# driver_board_one_module_pic_v3_1.net
KiCad netlist of a schematic drawn in EAGLE
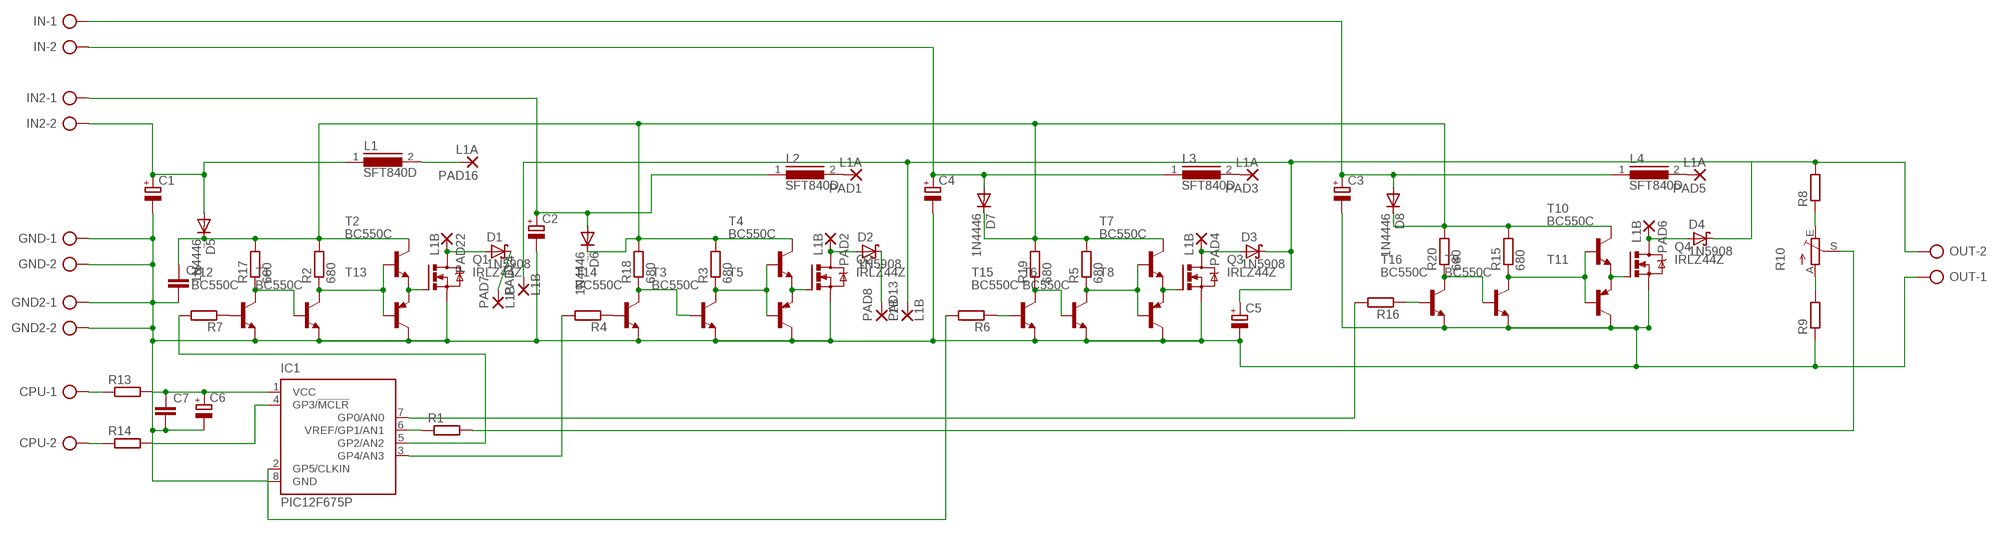
[diagram p0: schematic, sheet 1]

(export (version "E")
  (design (tool "Eeschema 10.0.6"))
  (components
    (comp (ref "C1")
      (value "CPOL-EUE5-8.5")
      (footprint "eagle-import:E5-8,5")
      (libsource (lib "eagle-import") (part "CPOL-EUE5-8.5"))
    )
    (comp (ref "C2")
      (value "CPOL-EUE5-8.5")
      (footprint "eagle-import:E5-8,5")
      (libsource (lib "eagle-import") (part "CPOL-EUE5-8.5"))
    )
    (comp (ref "C3")
      (value "CPOL-EUE5-8.5")
      (footprint "eagle-import:E5-8,5")
      (libsource (lib "eagle-import") (part "CPOL-EUE5-8.5"))
    )
    (comp (ref "C4")
      (value "CPOL-EUE5-8.5")
      (footprint "eagle-import:E5-8,5")
      (libsource (lib "eagle-import") (part "CPOL-EUE5-8.5"))
    )
    (comp (ref "C5")
      (value "CPOL-EUE5-8.5")
      (footprint "eagle-import:E5-8,5")
      (libsource (lib "eagle-import") (part "CPOL-EUE5-8.5"))
    )
    (comp (ref "C6")
      (value "CPOL-EUE5-8.5")
      (footprint "eagle-import:E5-8,5")
      (libsource (lib "eagle-import") (part "CPOL-EUE5-8.5"))
    )
    (comp (ref "C7")
      (value "C-EUC1206K")
      (footprint "eagle-import:C1206K")
      (libsource (lib "eagle-import") (part "C-EUC1206K"))
    )
    (comp (ref "C8")
      (value "C-EU050-045X075")
      (footprint "eagle-import:C050-045X075")
      (libsource (lib "eagle-import") (part "C-EU050-045X075"))
    )
    (comp (ref "CPU")
      (value "AK300/2")
      (footprint "eagle-import:AK300_2")
      (libsource (lib "eagle-import") (part "AK300/2"))
    )
    (comp (ref "D1")
      (value "1N5908")
      (footprint "eagle-import:C4111-15")
      (libsource (lib "eagle-import") (part "1N5908"))
    )
    (comp (ref "D2")
      (value "1N5908")
      (footprint "eagle-import:C4111-15")
      (libsource (lib "eagle-import") (part "1N5908"))
    )
    (comp (ref "D3")
      (value "1N5908")
      (footprint "eagle-import:C4111-15")
      (libsource (lib "eagle-import") (part "1N5908"))
    )
    (comp (ref "D4")
      (value "1N5908")
      (footprint "eagle-import:C4111-15")
      (libsource (lib "eagle-import") (part "1N5908"))
    )
    (comp (ref "D5")
      (value "1N4446")
      (footprint "eagle-import:DO35-10")
      (libsource (lib "eagle-import") (part "1N4446"))
    )
    (comp (ref "D6")
      (value "1N4446")
      (footprint "eagle-import:DO35-10")
      (libsource (lib "eagle-import") (part "1N4446"))
    )
    (comp (ref "D7")
      (value "1N4446")
      (footprint "eagle-import:DO35-10")
      (libsource (lib "eagle-import") (part "1N4446"))
    )
    (comp (ref "D8")
      (value "1N4446")
      (footprint "eagle-import:DO35-10")
      (libsource (lib "eagle-import") (part "1N4446"))
    )
    (comp (ref "GND")
      (value "AK300/2")
      (footprint "eagle-import:AK300_2")
      (libsource (lib "eagle-import") (part "AK300/2"))
    )
    (comp (ref "GND2")
      (value "AK300/2")
      (footprint "eagle-import:AK300_2")
      (libsource (lib "eagle-import") (part "AK300/2"))
    )
    (comp (ref "IC1")
      (value "PIC12F675P")
      (footprint "eagle-import:DIL8")
      (fields (field (name "MF") "MICROCHIP") (field (name "MPN") "PIC12F675-E/P"))
      (libsource (lib "eagle-import") (part "PIC12F675P"))
    )
    (comp (ref "IN")
      (value "AK300/2")
      (footprint "eagle-import:AK300_2")
      (libsource (lib "eagle-import") (part "AK300/2"))
    )
    (comp (ref "IN2")
      (value "AK300/2")
      (footprint "eagle-import:AK300_2")
      (libsource (lib "eagle-import") (part "AK300/2"))
    )
    (comp (ref "L1")
      (value "SFT840D")
      (footprint "eagle-import:SFT840D")
      (libsource (lib "eagle-import") (part "SFT840D"))
    )
    (comp (ref "L2")
      (value "SFT840D")
      (footprint "eagle-import:SFT840D")
      (libsource (lib "eagle-import") (part "SFT840D"))
    )
    (comp (ref "L3")
      (value "SFT840D")
      (footprint "eagle-import:SFT840D")
      (libsource (lib "eagle-import") (part "SFT840D"))
    )
    (comp (ref "L4")
      (value "SFT840D")
      (footprint "eagle-import:SFT840D")
      (libsource (lib "eagle-import") (part "SFT840D"))
    )
    (comp (ref "OUT")
      (value "AK300/2")
      (footprint "eagle-import:AK300_2")
      (libsource (lib "eagle-import") (part "AK300/2"))
    )
    (comp (ref "PAD1")
      (value "L1A")
      (footprint "eagle-import:3,81_1,1")
      (libsource (lib "eagle-import") (part "3,81/1,1"))
    )
    (comp (ref "PAD2")
      (value "L1B")
      (footprint "eagle-import:3,81_1,1")
      (libsource (lib "eagle-import") (part "3,81/1,1"))
    )
    (comp (ref "PAD3")
      (value "L1A")
      (footprint "eagle-import:3,81_1,1")
      (libsource (lib "eagle-import") (part "3,81/1,1"))
    )
    (comp (ref "PAD4")
      (value "L1B")
      (footprint "eagle-import:3,81_1,1")
      (libsource (lib "eagle-import") (part "3,81/1,1"))
    )
    (comp (ref "PAD5")
      (value "L1A")
      (footprint "eagle-import:3,81_1,1")
      (libsource (lib "eagle-import") (part "3,81/1,1"))
    )
    (comp (ref "PAD6")
      (value "L1B")
      (footprint "eagle-import:3,81_1,1")
      (libsource (lib "eagle-import") (part "3,81/1,1"))
    )
    (comp (ref "PAD7")
      (value "L1B")
      (footprint "eagle-import:3,81_1,1")
      (libsource (lib "eagle-import") (part "3,81/1,1"))
    )
    (comp (ref "PAD8")
      (value "L1B")
      (footprint "eagle-import:3,81_1,1")
      (libsource (lib "eagle-import") (part "3,81/1,1"))
    )
    (comp (ref "PAD13")
      (value "L1B")
      (footprint "eagle-import:3,81_1,1")
      (libsource (lib "eagle-import") (part "3,81/1,1"))
    )
    (comp (ref "PAD14")
      (value "L1B")
      (footprint "eagle-import:3,81_1,1")
      (libsource (lib "eagle-import") (part "3,81/1,1"))
    )
    (comp (ref "PAD16")
      (value "L1A")
      (footprint "eagle-import:3,81_1,1")
      (libsource (lib "eagle-import") (part "3,81/1,1"))
    )
    (comp (ref "PAD22")
      (value "L1B")
      (footprint "eagle-import:3,81_1,1")
      (libsource (lib "eagle-import") (part "3,81/1,1"))
    )
    (comp (ref "Q1")
      (value "IRLZ44Z")
      (footprint "eagle-import:TO220BH")
      (libsource (lib "eagle-import") (part "IRLZ44Z"))
    )
    (comp (ref "Q2")
      (value "IRLZ44Z")
      (footprint "eagle-import:TO220BH")
      (libsource (lib "eagle-import") (part "IRLZ44Z"))
    )
    (comp (ref "Q3")
      (value "IRLZ44Z")
      (footprint "eagle-import:TO220BH")
      (libsource (lib "eagle-import") (part "IRLZ44Z"))
    )
    (comp (ref "Q4")
      (value "IRLZ44Z")
      (footprint "eagle-import:TO220BH")
      (libsource (lib "eagle-import") (part "IRLZ44Z"))
    )
    (comp (ref "R1")
      (value "R-EU_0204/5")
      (footprint "eagle-import:0204_5")
      (libsource (lib "eagle-import") (part "resistor_R-EU_0204/5"))
    )
    (comp (ref "R2")
      (value "680")
      (footprint "eagle-import:0207_7")
      (libsource (lib "eagle-import") (part "resistor_R-EU_0207/7"))
    )
    (comp (ref "R3")
      (value "680")
      (footprint "eagle-import:0204_5")
      (libsource (lib "eagle-import") (part "resistor_R-EU_0204/5"))
    )
    (comp (ref "R4")
      (value "R-EU_0207/7")
      (footprint "eagle-import:0207_7")
      (libsource (lib "eagle-import") (part "resistor_R-EU_0207/7"))
    )
    (comp (ref "R5")
      (value "680")
      (footprint "eagle-import:0204_5")
      (libsource (lib "eagle-import") (part "resistor_R-EU_0204/5"))
    )
    (comp (ref "R6")
      (value "R-EU_0207/12")
      (footprint "eagle-import:0207_12")
      (libsource (lib "eagle-import") (part "resistor_R-EU_0207/12"))
    )
    (comp (ref "R7")
      (value "R-EU_0207/12")
      (footprint "eagle-import:0207_12")
      (libsource (lib "eagle-import") (part "resistor_R-EU_0207/12"))
    )
    (comp (ref "R8")
      (value "R-EU_0204/5")
      (footprint "eagle-import:0204_5")
      (libsource (lib "eagle-import") (part "resistor_R-EU_0204/5"))
    )
    (comp (ref "R9")
      (value "R-EU_0204/5")
      (footprint "eagle-import:0204_5")
      (libsource (lib "eagle-import") (part "resistor_R-EU_0204/5"))
    )
    (comp (ref "R10")
      (value "TRIM_EU-RJ9W")
      (footprint "eagle-import:RJ9W")
      (libsource (lib "eagle-import") (part "TRIM_EU-RJ9W"))
    )
    (comp (ref "R13")
      (value "R-EU_0204/5")
      (footprint "eagle-import:0204_5")
      (libsource (lib "eagle-import") (part "resistor_R-EU_0204/5"))
    )
    (comp (ref "R14")
      (value "R-EU_0204/5")
      (footprint "eagle-import:0204_5")
      (libsource (lib "eagle-import") (part "resistor_R-EU_0204/5"))
    )
    (comp (ref "R15")
      (value "680")
      (footprint "eagle-import:0204_5")
      (libsource (lib "eagle-import") (part "resistor_R-EU_0204/5"))
    )
    (comp (ref "R16")
      (value "R-EU_0207/10")
      (footprint "eagle-import:0207_10")
      (libsource (lib "eagle-import") (part "R-EU_0207/10"))
    )
    (comp (ref "R17")
      (value "680")
      (footprint "eagle-import:0204_5")
      (libsource (lib "eagle-import") (part "resistor_R-EU_0204/5"))
    )
    (comp (ref "R18")
      (value "680")
      (footprint "eagle-import:0204_5")
      (libsource (lib "eagle-import") (part "resistor_R-EU_0204/5"))
    )
    (comp (ref "R19")
      (value "680")
      (footprint "eagle-import:0204_5")
      (libsource (lib "eagle-import") (part "resistor_R-EU_0204/5"))
    )
    (comp (ref "R20")
      (value "680")
      (footprint "eagle-import:0204_5")
      (libsource (lib "eagle-import") (part "resistor_R-EU_0204/5"))
    )
    (comp (ref "T1")
      (value "BC550C")
      (footprint "eagle-import:TO92-EBC")
      (libsource (lib "eagle-import") (part "BC550C"))
    )
    (comp (ref "T2")
      (value "BC550C")
      (footprint "eagle-import:TO92-EBC")
      (libsource (lib "eagle-import") (part "BC550C"))
    )
    (comp (ref "T3")
      (value "BC550C")
      (footprint "eagle-import:TO92-EBC")
      (libsource (lib "eagle-import") (part "BC550C"))
    )
    (comp (ref "T4")
      (value "BC550C")
      (footprint "eagle-import:TO92-EBC")
      (libsource (lib "eagle-import") (part "BC550C"))
    )
    (comp (ref "T5")
      (value "BC557C-PNP-TO92-EBC")
      (footprint "eagle-import:TO92-EBC")
      (libsource (lib "eagle-import") (part "-PNP-TO92-EBCBC557C"))
    )
    (comp (ref "T6")
      (value "BC550C")
      (footprint "eagle-import:TO92-EBC")
      (libsource (lib "eagle-import") (part "BC550C"))
    )
    (comp (ref "T7")
      (value "BC550C")
      (footprint "eagle-import:TO92-EBC")
      (libsource (lib "eagle-import") (part "BC550C"))
    )
    (comp (ref "T8")
      (value "BC557C-PNP-TO92-EBC")
      (footprint "eagle-import:TO92-EBC")
      (libsource (lib "eagle-import") (part "-PNP-TO92-EBCBC557C"))
    )
    (comp (ref "T9")
      (value "BC550C")
      (footprint "eagle-import:TO92-EBC")
      (libsource (lib "eagle-import") (part "BC550C"))
    )
    (comp (ref "T10")
      (value "BC550C")
      (footprint "eagle-import:TO92-EBC")
      (libsource (lib "eagle-import") (part "BC550C"))
    )
    (comp (ref "T11")
      (value "BC557C-PNP-TO92-EBC")
      (footprint "eagle-import:TO92-EBC")
      (libsource (lib "eagle-import") (part "-PNP-TO92-EBCBC557C"))
    )
    (comp (ref "T12")
      (value "BC550C")
      (footprint "eagle-import:TO92-EBC")
      (libsource (lib "eagle-import") (part "BC550C"))
    )
    (comp (ref "T13")
      (value "BC557C-PNP-TO92-EBC")
      (footprint "eagle-import:TO92-EBC")
      (libsource (lib "eagle-import") (part "-PNP-TO92-EBCBC557C"))
    )
    (comp (ref "T14")
      (value "BC550C")
      (footprint "eagle-import:TO92-EBC")
      (libsource (lib "eagle-import") (part "BC550C"))
    )
    (comp (ref "T15")
      (value "BC550C")
      (footprint "eagle-import:TO92-EBC")
      (libsource (lib "eagle-import") (part "BC550C"))
    )
    (comp (ref "T16")
      (value "BC550C")
      (footprint "eagle-import:TO92-EBC")
      (libsource (lib "eagle-import") (part "BC550C"))
    )
  )
  (nets
    (net (code "1") (name "Net-(C8-Pad1)") (class "Default")
      (node (ref "C8") (pin "1") (pinfunction "1_1") (pintype "passive"))
      (node (ref "D5") (pin "C") (pinfunction "C_C") (pintype "passive"))
      (node (ref "D6") (pin "C") (pinfunction "C_C") (pintype "passive"))
      (node (ref "D7") (pin "C") (pinfunction "C_C") (pintype "passive"))
      (node (ref "D8") (pin "C") (pinfunction "C_C") (pintype "passive"))
      (node (ref "R15") (pin "2") (pinfunction "2_2") (pintype "passive"))
      (node (ref "R17") (pin "2") (pinfunction "2_2") (pintype "passive"))
      (node (ref "R18") (pin "2") (pinfunction "2_2") (pintype "passive"))
      (node (ref "R19") (pin "2") (pinfunction "2_2") (pintype "passive"))
      (node (ref "R2") (pin "2") (pinfunction "2_2") (pintype "passive"))
      (node (ref "R20") (pin "2") (pinfunction "2_2") (pintype "passive"))
      (node (ref "R3") (pin "2") (pinfunction "2_2") (pintype "passive"))
      (node (ref "R5") (pin "2") (pinfunction "2_2") (pintype "passive"))
      (node (ref "T10") (pin "C") (pinfunction "C_C") (pintype "passive"))
      (node (ref "T2") (pin "C") (pinfunction "C_C") (pintype "passive"))
      (node (ref "T4") (pin "C") (pinfunction "C_C") (pintype "passive"))
      (node (ref "T7") (pin "C") (pinfunction "C_C") (pintype "passive"))
    )
    (net (code "2") (name "Net-(CPUA-KL)") (class "Default")
      (node (ref "CPU") (pin "1") (pinfunction "KL_1") (pintype "passive"))
      (node (ref "R13") (pin "1") (pinfunction "1_1") (pintype "passive"))
    )
    (net (code "3") (name "Net-(CPUB-KL)") (class "Default")
      (node (ref "CPU") (pin "2") (pinfunction "KL_2") (pintype "passive"))
      (node (ref "R14") (pin "1") (pinfunction "1_1") (pintype "passive"))
    )
    (net (code "4") (name "Net-(GND2A-KL)") (class "Default")
      (node (ref "C1") (pin "-") (pinfunction "-_-") (pintype "passive"))
      (node (ref "C2") (pin "-") (pinfunction "-_-") (pintype "passive"))
      (node (ref "C3") (pin "-") (pinfunction "-_-") (pintype "passive"))
      (node (ref "C4") (pin "-") (pinfunction "-_-") (pintype "passive"))
      (node (ref "C5") (pin "-") (pinfunction "-_-") (pintype "passive"))
      (node (ref "C6") (pin "-") (pinfunction "-_-") (pintype "passive"))
      (node (ref "C7") (pin "2") (pinfunction "2_2") (pintype "passive"))
      (node (ref "C8") (pin "2") (pinfunction "2_2") (pintype "passive"))
      (node (ref "GND") (pin "1") (pinfunction "KL_1") (pintype "passive"))
      (node (ref "GND") (pin "2") (pinfunction "KL_2") (pintype "passive"))
      (node (ref "GND2") (pin "1") (pinfunction "KL_1") (pintype "passive"))
      (node (ref "GND2") (pin "2") (pinfunction "KL_2") (pintype "passive"))
      (node (ref "IC1") (pin "8") (pinfunction "GND_8") (pintype "power_in"))
      (node (ref "OUT") (pin "1") (pinfunction "KL_1") (pintype "passive"))
      (node (ref "Q1") (pin "S") (pinfunction "S_S") (pintype "passive"))
      (node (ref "Q2") (pin "S") (pinfunction "S_S") (pintype "passive"))
      (node (ref "Q3") (pin "S") (pinfunction "S_S") (pintype "passive"))
      (node (ref "Q4") (pin "S") (pinfunction "S_S") (pintype "passive"))
      (node (ref "R9") (pin "1") (pinfunction "1_1") (pintype "passive"))
      (node (ref "T1") (pin "E") (pinfunction "E_E") (pintype "passive"))
      (node (ref "T11") (pin "C") (pinfunction "C_C") (pintype "passive"))
      (node (ref "T12") (pin "E") (pinfunction "E_E") (pintype "passive"))
      (node (ref "T13") (pin "C") (pinfunction "C_C") (pintype "passive"))
      (node (ref "T14") (pin "E") (pinfunction "E_E") (pintype "passive"))
      (node (ref "T15") (pin "E") (pinfunction "E_E") (pintype "passive"))
      (node (ref "T16") (pin "E") (pinfunction "E_E") (pintype "passive"))
      (node (ref "T3") (pin "E") (pinfunction "E_E") (pintype "passive"))
      (node (ref "T5") (pin "C") (pinfunction "C_C") (pintype "passive"))
      (node (ref "T6") (pin "E") (pinfunction "E_E") (pintype "passive"))
      (node (ref "T8") (pin "C") (pinfunction "C_C") (pintype "passive"))
      (node (ref "T9") (pin "E") (pinfunction "E_E") (pintype "passive"))
    )
    (net (code "5") (name "Net-(IC1-GP0{slash}AN0)") (class "Default")
      (node (ref "IC1") (pin "7") (pinfunction "GP0/AN0_7") (pintype "bidirectional"))
      (node (ref "R16") (pin "2") (pinfunction "2_2") (pintype "passive"))
    )
    (net (code "6") (name "Net-(IC1-GP2{slash}AN2)") (class "Default")
      (node (ref "IC1") (pin "5") (pinfunction "GP2/AN2_5") (pintype "bidirectional"))
      (node (ref "R7") (pin "2") (pinfunction "2_2") (pintype "passive"))
    )
    (net (code "7") (name "Net-(IC1-GP3{slash}~{MCLR})") (class "Default")
      (node (ref "IC1") (pin "4") (pinfunction "GP3/~{MCLR}_4") (pintype "input"))
      (node (ref "R14") (pin "2") (pinfunction "2_2") (pintype "passive"))
    )
    (net (code "8") (name "Net-(IC1-GP4{slash}AN3)") (class "Default")
      (node (ref "IC1") (pin "3") (pinfunction "GP4/AN3_3") (pintype "bidirectional"))
      (node (ref "R4") (pin "2") (pinfunction "2_2") (pintype "passive"))
    )
    (net (code "9") (name "Net-(IC1-GP5{slash}CLKIN)") (class "Default")
      (node (ref "IC1") (pin "2") (pinfunction "GP5/CLKIN_2") (pintype "bidirectional"))
      (node (ref "R6") (pin "2") (pinfunction "2_2") (pintype "passive"))
    )
    (net (code "10") (name "Net-(IC1-VCC)") (class "Default")
      (node (ref "C6") (pin "+") (pinfunction "+_+") (pintype "passive"))
      (node (ref "C7") (pin "1") (pinfunction "1_1") (pintype "passive"))
      (node (ref "IC1") (pin "1") (pinfunction "VCC_1") (pintype "power_in"))
      (node (ref "R13") (pin "2") (pinfunction "2_2") (pintype "passive"))
    )
    (net (code "11") (name "Net-(IC1-VREF{slash}GP1{slash}AN1)") (class "Default")
      (node (ref "IC1") (pin "6") (pinfunction "VREF/GP1/AN1_6") (pintype "bidirectional"))
      (node (ref "R1") (pin "1") (pinfunction "1_1") (pintype "passive"))
    )
    (net (code "12") (name "Net-(IN2A-KL)") (class "Default")
      (node (ref "C2") (pin "+") (pinfunction "+_+") (pintype "passive"))
      (node (ref "D6") (pin "A") (pinfunction "A_A") (pintype "passive"))
      (node (ref "IN2") (pin "1") (pinfunction "KL_1") (pintype "passive"))
      (node (ref "L2") (pin "1") (pinfunction "1_1") (pintype "passive"))
    )
    (net (code "13") (name "Net-(IN2B-KL)") (class "Default")
      (node (ref "C1") (pin "+") (pinfunction "+_+") (pintype "passive"))
      (node (ref "D5") (pin "A") (pinfunction "A_A") (pintype "passive"))
      (node (ref "IN2") (pin "2") (pinfunction "KL_2") (pintype "passive"))
      (node (ref "L1") (pin "1") (pinfunction "1_1") (pintype "passive"))
    )
    (net (code "14") (name "Net-(INA-KL)") (class "Default")
      (node (ref "C3") (pin "+") (pinfunction "+_+") (pintype "passive"))
      (node (ref "D8") (pin "A") (pinfunction "A_A") (pintype "passive"))
      (node (ref "IN") (pin "1") (pinfunction "KL_1") (pintype "passive"))
      (node (ref "L4") (pin "1") (pinfunction "1_1") (pintype "passive"))
    )
    (net (code "15") (name "Net-(INB-KL)") (class "Default")
      (node (ref "C4") (pin "+") (pinfunction "+_+") (pintype "passive"))
      (node (ref "D7") (pin "A") (pinfunction "A_A") (pintype "passive"))
      (node (ref "IN") (pin "2") (pinfunction "KL_2") (pintype "passive"))
      (node (ref "L3") (pin "1") (pinfunction "1_1") (pintype "passive"))
    )
    (net (code "16") (name "Net-(OUTB-KL)") (class "Default")
      (node (ref "C5") (pin "+") (pinfunction "+_+") (pintype "passive"))
      (node (ref "D3") (pin "C") (pinfunction "C_C") (pintype "passive"))
      (node (ref "D4") (pin "C") (pinfunction "C_C") (pintype "passive"))
      (node (ref "OUT") (pin "2") (pinfunction "KL_2") (pintype "passive"))
      (node (ref "PAD13") (pin "1") (pinfunction "P_1") (pintype "passive"))
      (node (ref "PAD14") (pin "1") (pinfunction "P_1") (pintype "passive"))
      (node (ref "R8") (pin "2") (pinfunction "2_2") (pintype "passive"))
    )
    (net (code "17") (name "Net-(PAD1-P)") (class "Default")
      (node (ref "L2") (pin "2") (pinfunction "2_2") (pintype "passive"))
      (node (ref "PAD1") (pin "1") (pinfunction "P_1") (pintype "passive"))
    )
    (net (code "18") (name "Net-(PAD2-P)") (class "Default")
      (node (ref "D2") (pin "A") (pinfunction "A_A") (pintype "passive"))
      (node (ref "PAD2") (pin "1") (pinfunction "P_1") (pintype "passive"))
      (node (ref "Q2") (pin "D") (pinfunction "D_D") (pintype "passive"))
    )
    (net (code "19") (name "Net-(PAD3-P)") (class "Default")
      (node (ref "L3") (pin "2") (pinfunction "2_2") (pintype "passive"))
      (node (ref "PAD3") (pin "1") (pinfunction "P_1") (pintype "passive"))
    )
    (net (code "20") (name "Net-(PAD4-P)") (class "Default")
      (node (ref "D3") (pin "A") (pinfunction "A_A") (pintype "passive"))
      (node (ref "PAD4") (pin "1") (pinfunction "P_1") (pintype "passive"))
      (node (ref "Q3") (pin "D") (pinfunction "D_D") (pintype "passive"))
    )
    (net (code "21") (name "Net-(PAD5-P)") (class "Default")
      (node (ref "L4") (pin "2") (pinfunction "2_2") (pintype "passive"))
      (node (ref "PAD5") (pin "1") (pinfunction "P_1") (pintype "passive"))
    )
    (net (code "22") (name "Net-(PAD6-P)") (class "Default")
      (node (ref "D4") (pin "A") (pinfunction "A_A") (pintype "passive"))
      (node (ref "PAD6") (pin "1") (pinfunction "P_1") (pintype "passive"))
      (node (ref "Q4") (pin "D") (pinfunction "D_D") (pintype "passive"))
    )
    (net (code "23") (name "Net-(PAD7-P)") (class "Default")
      (node (ref "D1") (pin "C") (pinfunction "C_C") (pintype "passive"))
      (node (ref "PAD7") (pin "1") (pinfunction "P_1") (pintype "passive"))
    )
    (net (code "24") (name "Net-(PAD8-P)") (class "Default")
      (node (ref "D2") (pin "C") (pinfunction "C_C") (pintype "passive"))
      (node (ref "PAD8") (pin "1") (pinfunction "P_1") (pintype "passive"))
    )
    (net (code "25") (name "Net-(PAD16-P)") (class "Default")
      (node (ref "L1") (pin "2") (pinfunction "2_2") (pintype "passive"))
      (node (ref "PAD16") (pin "1") (pinfunction "P_1") (pintype "passive"))
    )
    (net (code "26") (name "Net-(PAD22-P)") (class "Default")
      (node (ref "D1") (pin "A") (pinfunction "A_A") (pintype "passive"))
      (node (ref "PAD22") (pin "1") (pinfunction "P_1") (pintype "passive"))
      (node (ref "Q1") (pin "D") (pinfunction "D_D") (pintype "passive"))
    )
    (net (code "27") (name "Net-(Q1-PadG)") (class "Default")
      (node (ref "Q1") (pin "G") (pinfunction "G_G") (pintype "passive"))
      (node (ref "T13") (pin "E") (pinfunction "E_E") (pintype "passive"))
      (node (ref "T2") (pin "E") (pinfunction "E_E") (pintype "passive"))
    )
    (net (code "28") (name "Net-(Q2-PadG)") (class "Default")
      (node (ref "Q2") (pin "G") (pinfunction "G_G") (pintype "passive"))
      (node (ref "T4") (pin "E") (pinfunction "E_E") (pintype "passive"))
      (node (ref "T5") (pin "E") (pinfunction "E_E") (pintype "passive"))
    )
    (net (code "29") (name "Net-(Q3-PadG)") (class "Default")
      (node (ref "Q3") (pin "G") (pinfunction "G_G") (pintype "passive"))
      (node (ref "T7") (pin "E") (pinfunction "E_E") (pintype "passive"))
      (node (ref "T8") (pin "E") (pinfunction "E_E") (pintype "passive"))
    )
    (net (code "30") (name "Net-(Q4-PadG)") (class "Default")
      (node (ref "Q4") (pin "G") (pinfunction "G_G") (pintype "passive"))
      (node (ref "T10") (pin "E") (pinfunction "E_E") (pintype "passive"))
      (node (ref "T11") (pin "E") (pinfunction "E_E") (pintype "passive"))
    )
    (net (code "31") (name "Net-(R1-Pad2)") (class "Default")
      (node (ref "R1") (pin "2") (pinfunction "2_2") (pintype "passive"))
      (node (ref "R10") (pin "S") (pinfunction "S_S") (pintype "passive"))
    )
    (net (code "32") (name "Net-(R2-Pad1)") (class "Default")
      (node (ref "R2") (pin "1") (pinfunction "1_1") (pintype "passive"))
      (node (ref "T1") (pin "C") (pinfunction "C_C") (pintype "passive"))
      (node (ref "T13") (pin "B") (pinfunction "B_B") (pintype "passive"))
      (node (ref "T2") (pin "B") (pinfunction "B_B") (pintype "passive"))
    )
    (net (code "33") (name "Net-(R3-Pad1)") (class "Default")
      (node (ref "R3") (pin "1") (pinfunction "1_1") (pintype "passive"))
      (node (ref "T3") (pin "C") (pinfunction "C_C") (pintype "passive"))
      (node (ref "T4") (pin "B") (pinfunction "B_B") (pintype "passive"))
      (node (ref "T5") (pin "B") (pinfunction "B_B") (pintype "passive"))
    )
    (net (code "34") (name "Net-(R4-Pad1)") (class "Default")
      (node (ref "R4") (pin "1") (pinfunction "1_1") (pintype "passive"))
      (node (ref "T14") (pin "B") (pinfunction "B_B") (pintype "passive"))
    )
    (net (code "35") (name "Net-(R5-Pad1)") (class "Default")
      (node (ref "R5") (pin "1") (pinfunction "1_1") (pintype "passive"))
      (node (ref "T6") (pin "C") (pinfunction "C_C") (pintype "passive"))
      (node (ref "T7") (pin "B") (pinfunction "B_B") (pintype "passive"))
      (node (ref "T8") (pin "B") (pinfunction "B_B") (pintype "passive"))
    )
    (net (code "36") (name "Net-(R6-Pad1)") (class "Default")
      (node (ref "R6") (pin "1") (pinfunction "1_1") (pintype "passive"))
      (node (ref "T15") (pin "B") (pinfunction "B_B") (pintype "passive"))
    )
    (net (code "37") (name "Net-(R7-Pad1)") (class "Default")
      (node (ref "R7") (pin "1") (pinfunction "1_1") (pintype "passive"))
      (node (ref "T12") (pin "B") (pinfunction "B_B") (pintype "passive"))
    )
    (net (code "38") (name "Net-(R10-PadA)") (class "Default")
      (node (ref "R10") (pin "A") (pinfunction "A_A") (pintype "passive"))
      (node (ref "R9") (pin "2") (pinfunction "2_2") (pintype "passive"))
    )
    (net (code "39") (name "Net-(R10-PadE)") (class "Default")
      (node (ref "R10") (pin "E") (pinfunction "E_E") (pintype "passive"))
      (node (ref "R8") (pin "1") (pinfunction "1_1") (pintype "passive"))
    )
    (net (code "40") (name "Net-(R15-Pad1)") (class "Default")
      (node (ref "R15") (pin "1") (pinfunction "1_1") (pintype "passive"))
      (node (ref "T10") (pin "B") (pinfunction "B_B") (pintype "passive"))
      (node (ref "T11") (pin "B") (pinfunction "B_B") (pintype "passive"))
      (node (ref "T9") (pin "C") (pinfunction "C_C") (pintype "passive"))
    )
    (net (code "41") (name "Net-(R16-Pad1)") (class "Default")
      (node (ref "R16") (pin "1") (pinfunction "1_1") (pintype "passive"))
      (node (ref "T16") (pin "B") (pinfunction "B_B") (pintype "passive"))
    )
    (net (code "42") (name "Net-(R17-Pad1)") (class "Default")
      (node (ref "R17") (pin "1") (pinfunction "1_1") (pintype "passive"))
      (node (ref "T1") (pin "B") (pinfunction "B_B") (pintype "passive"))
      (node (ref "T12") (pin "C") (pinfunction "C_C") (pintype "passive"))
    )
    (net (code "43") (name "Net-(R18-Pad1)") (class "Default")
      (node (ref "R18") (pin "1") (pinfunction "1_1") (pintype "passive"))
      (node (ref "T14") (pin "C") (pinfunction "C_C") (pintype "passive"))
      (node (ref "T3") (pin "B") (pinfunction "B_B") (pintype "passive"))
    )
    (net (code "44") (name "Net-(R19-Pad1)") (class "Default")
      (node (ref "R19") (pin "1") (pinfunction "1_1") (pintype "passive"))
      (node (ref "T15") (pin "C") (pinfunction "C_C") (pintype "passive"))
      (node (ref "T6") (pin "B") (pinfunction "B_B") (pintype "passive"))
    )
    (net (code "45") (name "Net-(R20-Pad1)") (class "Default")
      (node (ref "R20") (pin "1") (pinfunction "1_1") (pintype "passive"))
      (node (ref "T16") (pin "C") (pinfunction "C_C") (pintype "passive"))
      (node (ref "T9") (pin "B") (pinfunction "B_B") (pintype "passive"))
    )
  )
)
